# FPGA.net
KiCad netlist of a schematic drawn in Altium Designer
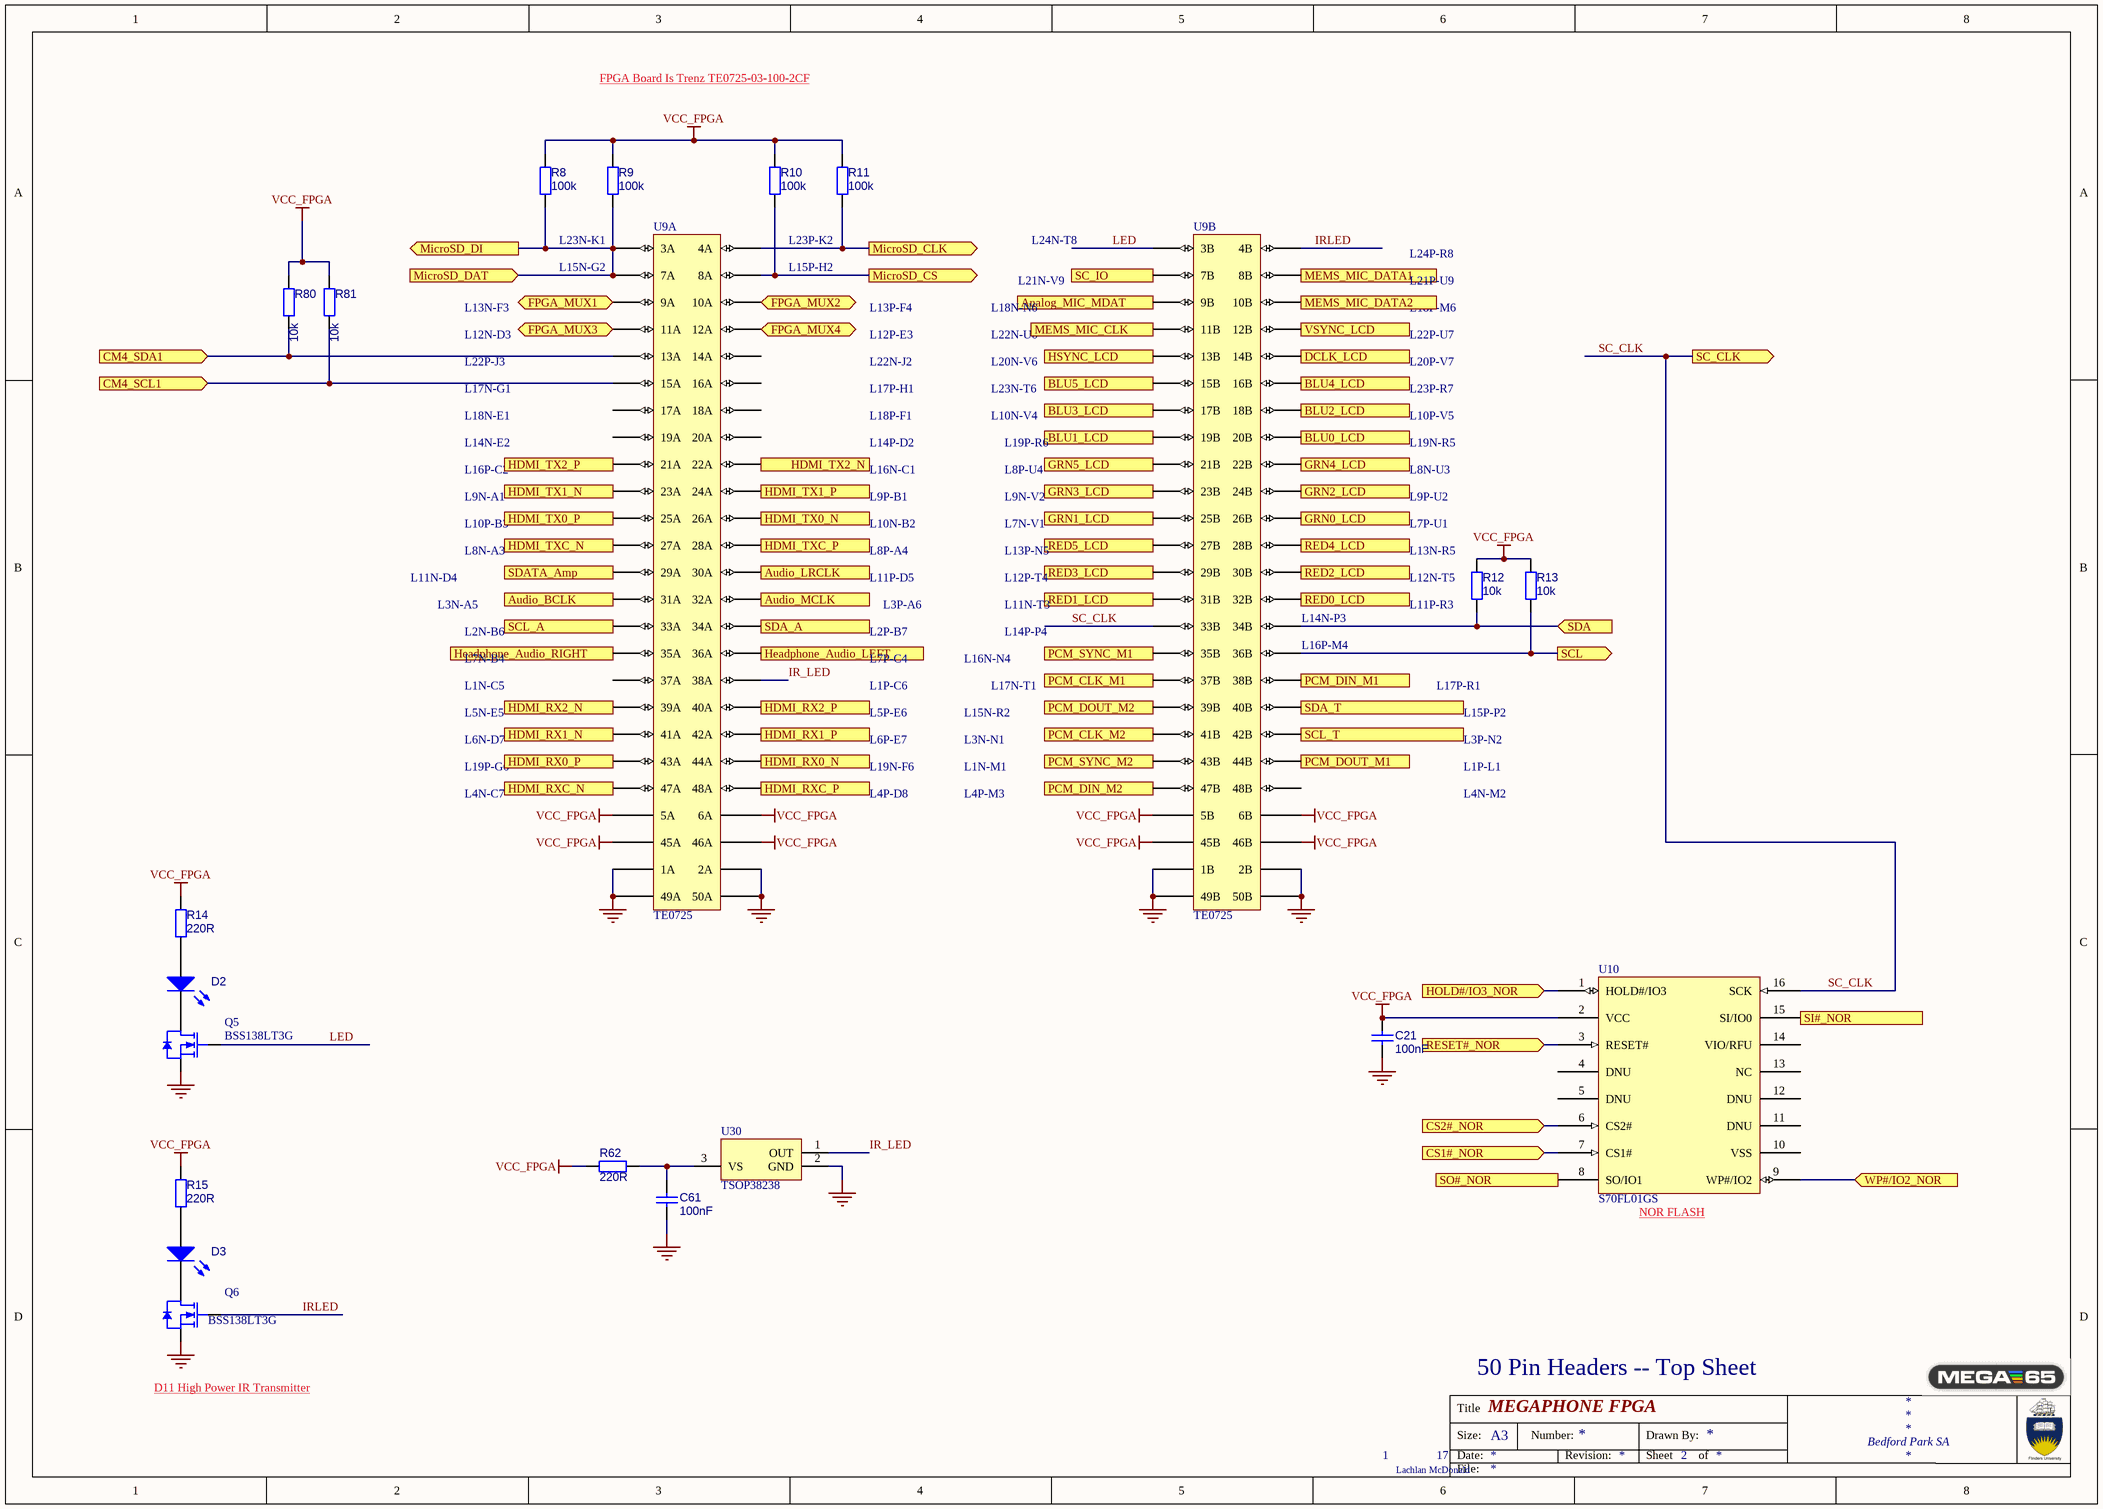
[diagram p0: FPGA.SchDoc]

(export (version "E")
  (design (tool "Eeschema 10.0.6"))
  (components
    (comp (ref "C21")
      (value "100nF")
      (footprint "0603_CAP UF HD")
      (description "Capacitor")
      (libsource (lib "Workshop Library 2010_06_24") (part "Cap"))
    )
    (comp (ref "C61")
      (value "100nF")
      (footprint "0603_CAP UF HD")
      (description "Capacitor")
      (libsource (lib "Workshop Library 2010_06_24") (part "Cap"))
    )
    (comp (ref "D2")
      (value "~")
      (footprint "LED 3mm Red")
      (description "LED")
      (libsource (lib "Workshop Library 2010_06_24") (part "LED"))
    )
    (comp (ref "D3")
      (value "~")
      (footprint "LED 3mm Red")
      (description "LED")
      (libsource (lib "Workshop Library 2010_06_24") (part "LED"))
    )
    (comp (ref "Q5")
      (value "BSS138LT3G")
      (footprint "SOT-23")
      (description "Power MOSFET, 200 mA, 50 V, N-Channel, 3-Pin SOT-23, Pb-Free, Tape and Reel")
      (fields
        (field (name "MANUFACTURER") "On Semiconductor")
        (field (name "ELEMENT 14 PART NUMBER") "1431319")
      )
      (libsource (lib "Workshop Library 2010_06_24") (part "BSS138LT3G"))
    )
    (comp (ref "Q6")
      (value "BSS138LT3G")
      (footprint "SOT-23")
      (description "Power MOSFET, 200 mA, 50 V, N-Channel, 3-Pin SOT-23, Pb-Free, Tape and Reel")
      (fields
        (field (name "MANUFACTURER") "On Semiconductor")
        (field (name "ELEMENT 14 PART NUMBER") "1431319")
      )
      (libsource (lib "Workshop Library 2010_06_24") (part "BSS138LT3G"))
    )
    (comp (ref "R8")
      (value "100k")
      (footprint "0603-RESISTOR HD")
      (description "Resistor")
      (libsource (lib "MEGAphone") (part "Resistor"))
    )
    (comp (ref "R9")
      (value "100k")
      (footprint "0603-RESISTOR HD")
      (description "Resistor")
      (libsource (lib "MEGAphone") (part "Resistor"))
    )
    (comp (ref "R10")
      (value "100k")
      (footprint "0603-RESISTOR HD")
      (description "Resistor")
      (libsource (lib "MEGAphone") (part "Resistor"))
    )
    (comp (ref "R11")
      (value "100k")
      (footprint "0603-RESISTOR HD")
      (description "Resistor")
      (libsource (lib "MEGAphone") (part "Resistor"))
    )
    (comp (ref "R12")
      (value "10k")
      (footprint "0603-RESISTOR HD")
      (description "Resistor")
      (libsource (lib "Workshop Library 2010_06_24") (part "Resistor"))
    )
    (comp (ref "R13")
      (value "10k")
      (footprint "0603-RESISTOR HD")
      (description "Resistor")
      (libsource (lib "Workshop Library 2010_06_24") (part "Resistor"))
    )
    (comp (ref "R14")
      (value "220R")
      (footprint "0603-RESISTOR HD")
      (description "Resistor")
      (libsource (lib "Workshop Library 2010_06_24") (part "Resistor"))
    )
    (comp (ref "R15")
      (value "220R")
      (footprint "0603-RESISTOR HD")
      (description "Resistor")
      (libsource (lib "Workshop Library 2010_06_24") (part "Resistor"))
    )
    (comp (ref "R62")
      (value "220R")
      (footprint "0603-RESISTOR HD")
      (description "Resistor")
      (libsource (lib "") (part "Resistor_1"))
    )
    (comp (ref "R80")
      (value "10k")
      (footprint "0603-RESISTOR HD")
      (description "Resistor")
      (libsource (lib "Workshop Library 2010_06_24") (part "Resistor"))
    )
    (comp (ref "R81")
      (value "10k")
      (footprint "0603-RESISTOR HD")
      (description "Resistor")
      (libsource (lib "Workshop Library 2010_06_24") (part "Resistor"))
    )
    (comp (ref "U9")
      (value "TE0725")
      (footprint "Trenz TE-0725")
      (description "FPGA Module Xilinx Artix-7 100T, optical transceiver")
      (fields (field (name "MANUFACTURER") "TE Connectivity"))
      (libsource (lib "Workshop Library 2010_06_24") (part "TRENZ TE0725"))
    )
    (comp (ref "U10")
      (value "S70FL01GS")
      (footprint "S70FL01GS")
      (fields (field (name "MANUFACTURER") "S70FL01GSDPMFI010"))
      (libsource (lib "Schlib1") (part "NOR Flash"))
    )
    (comp (ref "U30")
      (value "TSOP38238")
      (footprint "VISH-TSOP38238")
      (description "IR Receiver Modules for Remote Control System, 2.5 to 5.5 V, -25 to 85 degC, 3-Pin THD, RoHS, Bulk")
      (fields (field (name "TOLERANCE") "30ppm"))
      (libsource (lib "Altium Content Vault") (part "VISH-TSOP38238-3"))
    )
  )
  (nets
    (net (code "1") (name "/Analog_MIC_MDAT") (class "Default")
      (node (ref "U9") (pin "9B") (pinfunction "9B_9B") (pintype "bidirectional"))
    )
    (net (code "2") (name "/Audio_BCLK") (class "Default")
      (node (ref "U9") (pin "31A") (pinfunction "31A_31A") (pintype "bidirectional"))
    )
    (net (code "3") (name "/Audio_LRCLK") (class "Default")
      (node (ref "U9") (pin "30A") (pinfunction "30A_30A") (pintype "bidirectional"))
    )
    (net (code "4") (name "/Audio_MCLK") (class "Default")
      (node (ref "U9") (pin "32A") (pinfunction "32A_32A") (pintype "bidirectional"))
    )
    (net (code "5") (name "/BLU0_LCD") (class "Default")
      (node (ref "U9") (pin "20B") (pinfunction "20B_20B") (pintype "bidirectional"))
    )
    (net (code "6") (name "/BLU1_LCD") (class "Default")
      (node (ref "U9") (pin "19B") (pinfunction "19B_19B") (pintype "bidirectional"))
    )
    (net (code "7") (name "/BLU2_LCD") (class "Default")
      (node (ref "U9") (pin "18B") (pinfunction "18B_18B") (pintype "bidirectional"))
    )
    (net (code "8") (name "/BLU3_LCD") (class "Default")
      (node (ref "U9") (pin "17B") (pinfunction "17B_17B") (pintype "bidirectional"))
    )
    (net (code "9") (name "/BLU4_LCD") (class "Default")
      (node (ref "U9") (pin "16B") (pinfunction "16B_16B") (pintype "bidirectional"))
    )
    (net (code "10") (name "/BLU5_LCD") (class "Default")
      (node (ref "U9") (pin "15B") (pinfunction "15B_15B") (pintype "bidirectional"))
    )
    (net (code "11") (name "/CM4_SCL1") (class "Default")
      (node (ref "R81") (pin "2") (pinfunction "2_2") (pintype "passive"))
      (node (ref "U9") (pin "15A") (pinfunction "15A_15A") (pintype "bidirectional"))
    )
    (net (code "12") (name "/CM4_SDA1") (class "Default")
      (node (ref "R80") (pin "2") (pinfunction "2_2") (pintype "passive"))
      (node (ref "U9") (pin "13A") (pinfunction "13A_13A") (pintype "bidirectional"))
    )
    (net (code "13") (name "/CS1#_NOR") (class "Default")
      (node (ref "U10") (pin "7") (pinfunction "CS1#_7") (pintype "input"))
    )
    (net (code "14") (name "/CS2#_NOR") (class "Default")
      (node (ref "U10") (pin "6") (pinfunction "CS2#_6") (pintype "input"))
    )
    (net (code "15") (name "/DCLK_LCD") (class "Default")
      (node (ref "U9") (pin "14B") (pinfunction "14B_14B") (pintype "bidirectional"))
    )
    (net (code "16") (name "/FPGA_MUX1") (class "Default")
      (node (ref "U9") (pin "9A") (pinfunction "9A_9A") (pintype "bidirectional"))
    )
    (net (code "17") (name "/FPGA_MUX2") (class "Default")
      (node (ref "U9") (pin "10A") (pinfunction "10A_10A") (pintype "bidirectional"))
    )
    (net (code "18") (name "/FPGA_MUX3") (class "Default")
      (node (ref "U9") (pin "11A") (pinfunction "11A_11A") (pintype "bidirectional"))
    )
    (net (code "19") (name "/FPGA_MUX4") (class "Default")
      (node (ref "U9") (pin "12A") (pinfunction "12A_12A") (pintype "bidirectional"))
    )
    (net (code "20") (name "/GRN0_LCD") (class "Default")
      (node (ref "U9") (pin "26B") (pinfunction "26B_26B") (pintype "bidirectional"))
    )
    (net (code "21") (name "/GRN1_LCD") (class "Default")
      (node (ref "U9") (pin "25B") (pinfunction "25B_25B") (pintype "bidirectional"))
    )
    (net (code "22") (name "/GRN2_LCD") (class "Default")
      (node (ref "U9") (pin "24B") (pinfunction "24B_24B") (pintype "bidirectional"))
    )
    (net (code "23") (name "/GRN3_LCD") (class "Default")
      (node (ref "U9") (pin "23B") (pinfunction "23B_23B") (pintype "bidirectional"))
    )
    (net (code "24") (name "/GRN4_LCD") (class "Default")
      (node (ref "U9") (pin "22B") (pinfunction "22B_22B") (pintype "bidirectional"))
    )
    (net (code "25") (name "/GRN5_LCD") (class "Default")
      (node (ref "U9") (pin "21B") (pinfunction "21B_21B") (pintype "bidirectional"))
    )
    (net (code "26") (name "/HDMI_RX0_N") (class "Default")
      (node (ref "U9") (pin "44A") (pinfunction "44A_44A") (pintype "bidirectional"))
    )
    (net (code "27") (name "/HDMI_RX0_P") (class "Default")
      (node (ref "U9") (pin "43A") (pinfunction "43A_43A") (pintype "bidirectional"))
    )
    (net (code "28") (name "/HDMI_RX1_N") (class "Default")
      (node (ref "U9") (pin "41A") (pinfunction "41A_41A") (pintype "bidirectional"))
    )
    (net (code "29") (name "/HDMI_RX1_P") (class "Default")
      (node (ref "U9") (pin "42A") (pinfunction "42A_42A") (pintype "bidirectional"))
    )
    (net (code "30") (name "/HDMI_RX2_N") (class "Default")
      (node (ref "U9") (pin "39A") (pinfunction "39A_39A") (pintype "bidirectional"))
    )
    (net (code "31") (name "/HDMI_RX2_P") (class "Default")
      (node (ref "U9") (pin "40A") (pinfunction "40A_40A") (pintype "bidirectional"))
    )
    (net (code "32") (name "/HDMI_RXC_N") (class "Default")
      (node (ref "U9") (pin "47A") (pinfunction "47A_47A") (pintype "bidirectional"))
    )
    (net (code "33") (name "/HDMI_RXC_P") (class "Default")
      (node (ref "U9") (pin "48A") (pinfunction "48A_48A") (pintype "bidirectional"))
    )
    (net (code "34") (name "/HDMI_TX0_N") (class "Default")
      (node (ref "U9") (pin "26A") (pinfunction "26A_26A") (pintype "bidirectional"))
    )
    (net (code "35") (name "/HDMI_TX0_P") (class "Default")
      (node (ref "U9") (pin "25A") (pinfunction "25A_25A") (pintype "bidirectional"))
    )
    (net (code "36") (name "/HDMI_TX1_N") (class "Default")
      (node (ref "U9") (pin "23A") (pinfunction "23A_23A") (pintype "bidirectional"))
    )
    (net (code "37") (name "/HDMI_TX1_P") (class "Default")
      (node (ref "U9") (pin "24A") (pinfunction "24A_24A") (pintype "bidirectional"))
    )
    (net (code "38") (name "/HDMI_TX2_N") (class "Default")
      (node (ref "U9") (pin "22A") (pinfunction "22A_22A") (pintype "bidirectional"))
    )
    (net (code "39") (name "/HDMI_TX2_P") (class "Default")
      (node (ref "U9") (pin "21A") (pinfunction "21A_21A") (pintype "bidirectional"))
    )
    (net (code "40") (name "/HDMI_TXC_N") (class "Default")
      (node (ref "U9") (pin "27A") (pinfunction "27A_27A") (pintype "bidirectional"))
    )
    (net (code "41") (name "/HDMI_TXC_P") (class "Default")
      (node (ref "U9") (pin "28A") (pinfunction "28A_28A") (pintype "bidirectional"))
    )
    (net (code "42") (name "/HOLD#{slash}IO3_NOR") (class "Default")
      (node (ref "U10") (pin "1") (pinfunction "HOLD#/IO3_1") (pintype "bidirectional"))
    )
    (net (code "43") (name "/HSYNC_LCD") (class "Default")
      (node (ref "U9") (pin "13B") (pinfunction "13B_13B") (pintype "bidirectional"))
    )
    (net (code "44") (name "/Headphone_Audio_LEFT") (class "Default")
      (node (ref "U9") (pin "36A") (pinfunction "36A_36A") (pintype "bidirectional"))
    )
    (net (code "45") (name "/Headphone_Audio_RIGHT") (class "Default")
      (node (ref "U9") (pin "35A") (pinfunction "35A_35A") (pintype "bidirectional"))
    )
    (net (code "46") (name "/IRLED") (class "Default")
      (node (ref "Q6") (pin "1") (pinfunction "G_1") (pintype "passive"))
      (node (ref "U9") (pin "4B") (pinfunction "4B_4B") (pintype "bidirectional"))
    )
    (net (code "47") (name "/IR_LED") (class "Default")
      (node (ref "U30") (pin "1") (pinfunction "OUT_1") (pintype "power_in"))
      (node (ref "U9") (pin "38A") (pinfunction "38A_38A") (pintype "bidirectional"))
    )
    (net (code "48") (name "/LED") (class "Default")
      (node (ref "Q5") (pin "1") (pinfunction "G_1") (pintype "passive"))
      (node (ref "U9") (pin "3B") (pinfunction "3B_3B") (pintype "bidirectional"))
    )
    (net (code "49") (name "/MEMS_MIC_CLK") (class "Default")
      (node (ref "U9") (pin "11B") (pinfunction "11B_11B") (pintype "bidirectional"))
    )
    (net (code "50") (name "/MEMS_MIC_DATA1") (class "Default")
      (node (ref "U9") (pin "8B") (pinfunction "8B_8B") (pintype "bidirectional"))
    )
    (net (code "51") (name "/MEMS_MIC_DATA2") (class "Default")
      (node (ref "U9") (pin "10B") (pinfunction "10B_10B") (pintype "bidirectional"))
    )
    (net (code "52") (name "/MicroSD_CLK") (class "Default")
      (node (ref "R11") (pin "2") (pinfunction "2_2") (pintype "passive"))
      (node (ref "U9") (pin "4A") (pinfunction "4A_4A") (pintype "bidirectional"))
    )
    (net (code "53") (name "/MicroSD_CS") (class "Default")
      (node (ref "R10") (pin "2") (pinfunction "2_2") (pintype "passive"))
      (node (ref "U9") (pin "8A") (pinfunction "8A_8A") (pintype "bidirectional"))
    )
    (net (code "54") (name "/MicroSD_DAT") (class "Default")
      (node (ref "R8") (pin "2") (pinfunction "2_2") (pintype "passive"))
      (node (ref "R9") (pin "2") (pinfunction "2_2") (pintype "passive"))
      (node (ref "U9") (pin "3A") (pinfunction "3A_3A") (pintype "bidirectional"))
      (node (ref "U9") (pin "7A") (pinfunction "7A_7A") (pintype "bidirectional"))
    )
    (net (code "55") (name "/PCM_CLK_M1") (class "Default")
      (node (ref "U9") (pin "37B") (pinfunction "37B_37B") (pintype "bidirectional"))
    )
    (net (code "56") (name "/PCM_CLK_M2") (class "Default")
      (node (ref "U9") (pin "41B") (pinfunction "41B_41B") (pintype "bidirectional"))
    )
    (net (code "57") (name "/PCM_DIN_M1") (class "Default")
      (node (ref "U9") (pin "38B") (pinfunction "38B_38B") (pintype "bidirectional"))
    )
    (net (code "58") (name "/PCM_DIN_M2") (class "Default")
      (node (ref "U9") (pin "47B") (pinfunction "47B_47B") (pintype "bidirectional"))
    )
    (net (code "59") (name "/PCM_DOUT_M1") (class "Default")
      (node (ref "U9") (pin "44B") (pinfunction "44B_44B") (pintype "bidirectional"))
    )
    (net (code "60") (name "/PCM_DOUT_M2") (class "Default")
      (node (ref "U9") (pin "39B") (pinfunction "39B_39B") (pintype "bidirectional"))
    )
    (net (code "61") (name "/PCM_SYNC_M1") (class "Default")
      (node (ref "U9") (pin "35B") (pinfunction "35B_35B") (pintype "bidirectional"))
    )
    (net (code "62") (name "/PCM_SYNC_M2") (class "Default")
      (node (ref "U9") (pin "43B") (pinfunction "43B_43B") (pintype "bidirectional"))
    )
    (net (code "63") (name "/RED0_LCD") (class "Default")
      (node (ref "U9") (pin "32B") (pinfunction "32B_32B") (pintype "bidirectional"))
    )
    (net (code "64") (name "/RED1_LCD") (class "Default")
      (node (ref "U9") (pin "31B") (pinfunction "31B_31B") (pintype "bidirectional"))
    )
    (net (code "65") (name "/RED2_LCD") (class "Default")
      (node (ref "U9") (pin "30B") (pinfunction "30B_30B") (pintype "bidirectional"))
    )
    (net (code "66") (name "/RED3_LCD") (class "Default")
      (node (ref "U9") (pin "29B") (pinfunction "29B_29B") (pintype "bidirectional"))
    )
    (net (code "67") (name "/RED4_LCD") (class "Default")
      (node (ref "U9") (pin "28B") (pinfunction "28B_28B") (pintype "bidirectional"))
    )
    (net (code "68") (name "/RED5_LCD") (class "Default")
      (node (ref "U9") (pin "27B") (pinfunction "27B_27B") (pintype "bidirectional"))
    )
    (net (code "69") (name "/RESET#_NOR") (class "Default")
      (node (ref "U10") (pin "3") (pinfunction "RESET#_3") (pintype "input"))
    )
    (net (code "70") (name "/SCL") (class "Default")
      (node (ref "R13") (pin "2") (pinfunction "2_2") (pintype "passive"))
      (node (ref "U9") (pin "36B") (pinfunction "36B_36B") (pintype "bidirectional"))
    )
    (net (code "71") (name "/SCL_A") (class "Default")
      (node (ref "U9") (pin "33A") (pinfunction "33A_33A") (pintype "bidirectional"))
    )
    (net (code "72") (name "/SCL_T") (class "Default")
      (node (ref "U9") (pin "42B") (pinfunction "42B_42B") (pintype "bidirectional"))
    )
    (net (code "73") (name "/SC_CLK") (class "Default")
      (node (ref "U10") (pin "16") (pinfunction "SCK_16") (pintype "input"))
      (node (ref "U9") (pin "33B") (pinfunction "33B_33B") (pintype "bidirectional"))
    )
    (net (code "74") (name "/SC_IO") (class "Default")
      (node (ref "U9") (pin "7B") (pinfunction "7B_7B") (pintype "bidirectional"))
    )
    (net (code "75") (name "/SDA") (class "Default")
      (node (ref "R12") (pin "2") (pinfunction "2_2") (pintype "passive"))
      (node (ref "U9") (pin "34B") (pinfunction "34B_34B") (pintype "bidirectional"))
    )
    (net (code "76") (name "/SDATA_Amp") (class "Default")
      (node (ref "U9") (pin "29A") (pinfunction "29A_29A") (pintype "bidirectional"))
    )
    (net (code "77") (name "/SDA_A") (class "Default")
      (node (ref "U9") (pin "34A") (pinfunction "34A_34A") (pintype "bidirectional"))
    )
    (net (code "78") (name "/SDA_T") (class "Default")
      (node (ref "U9") (pin "40B") (pinfunction "40B_40B") (pintype "bidirectional"))
    )
    (net (code "79") (name "/SI#_NOR") (class "Default")
      (node (ref "U10") (pin "15") (pinfunction "SI/IO0_15") (pintype "passive"))
    )
    (net (code "80") (name "/SO#_NOR") (class "Default")
      (node (ref "U10") (pin "8") (pinfunction "SO/IO1_8") (pintype "passive"))
    )
    (net (code "81") (name "/VSYNC_LCD") (class "Default")
      (node (ref "U9") (pin "12B") (pinfunction "12B_12B") (pintype "bidirectional"))
    )
    (net (code "82") (name "/WP#{slash}IO2_NOR") (class "Default")
      (node (ref "U10") (pin "9") (pinfunction "WP#/IO2_9") (pintype "bidirectional"))
    )
    (net (code "83") (name "GND") (class "Default")
      (node (ref "C21") (pin "2") (pinfunction "2_2") (pintype "passive"))
      (node (ref "C61") (pin "2") (pinfunction "2_2") (pintype "passive"))
      (node (ref "Q5") (pin "2") (pinfunction "S_2") (pintype "passive"))
      (node (ref "Q6") (pin "2") (pinfunction "S_2") (pintype "passive"))
      (node (ref "U30") (pin "2") (pinfunction "GND_2") (pintype "power_in"))
      (node (ref "U9") (pin "1A") (pinfunction "1A_1A") (pintype "power_in"))
      (node (ref "U9") (pin "1B") (pinfunction "1B_1B") (pintype "power_in"))
      (node (ref "U9") (pin "2A") (pinfunction "2A_2A") (pintype "power_in"))
      (node (ref "U9") (pin "2B") (pinfunction "2B_2B") (pintype "power_in"))
      (node (ref "U9") (pin "49A") (pinfunction "49A_49A") (pintype "power_in"))
      (node (ref "U9") (pin "49B") (pinfunction "49B_49B") (pintype "power_in"))
      (node (ref "U9") (pin "50A") (pinfunction "50A_50A") (pintype "power_in"))
      (node (ref "U9") (pin "50B") (pinfunction "50B_50B") (pintype "power_in"))
    )
    (net (code "84") (name "Net-(D2-PadA)") (class "Default")
      (node (ref "D2") (pin "A") (pinfunction "A_A") (pintype "passive"))
      (node (ref "R14") (pin "2") (pinfunction "2_2") (pintype "passive"))
    )
    (net (code "85") (name "Net-(D3-PadA)") (class "Default")
      (node (ref "D3") (pin "A") (pinfunction "A_A") (pintype "passive"))
      (node (ref "R15") (pin "2") (pinfunction "2_2") (pintype "passive"))
    )
    (net (code "86") (name "Net-(Q5-D)") (class "Default")
      (node (ref "D2") (pin "K") (pinfunction "K_K") (pintype "passive"))
      (node (ref "Q5") (pin "3") (pinfunction "D_3") (pintype "passive"))
    )
    (net (code "87") (name "Net-(Q6-D)") (class "Default")
      (node (ref "D3") (pin "K") (pinfunction "K_K") (pintype "passive"))
      (node (ref "Q6") (pin "3") (pinfunction "D_3") (pintype "passive"))
    )
    (net (code "88") (name "Net-(U30-VS)") (class "Default")
      (node (ref "C61") (pin "1") (pinfunction "1_1") (pintype "passive"))
      (node (ref "R62") (pin "2") (pinfunction "2_2") (pintype "passive"))
      (node (ref "U30") (pin "3") (pinfunction "VS_3") (pintype "power_in"))
    )
    (net (code "89") (name "VCC_FPGA") (class "Default")
      (node (ref "C21") (pin "1") (pinfunction "1_1") (pintype "passive"))
      (node (ref "R10") (pin "1") (pinfunction "1_1") (pintype "passive"))
      (node (ref "R11") (pin "1") (pinfunction "1_1") (pintype "passive"))
      (node (ref "R12") (pin "1") (pinfunction "1_1") (pintype "passive"))
      (node (ref "R13") (pin "1") (pinfunction "1_1") (pintype "passive"))
      (node (ref "R14") (pin "1") (pinfunction "1_1") (pintype "passive"))
      (node (ref "R15") (pin "1") (pinfunction "1_1") (pintype "passive"))
      (node (ref "R62") (pin "1") (pinfunction "1_1") (pintype "passive"))
      (node (ref "R8") (pin "1") (pinfunction "1_1") (pintype "passive"))
      (node (ref "R80") (pin "1") (pinfunction "1_1") (pintype "passive"))
      (node (ref "R81") (pin "1") (pinfunction "1_1") (pintype "passive"))
      (node (ref "R9") (pin "1") (pinfunction "1_1") (pintype "passive"))
      (node (ref "U10") (pin "2") (pinfunction "VCC_2") (pintype "power_in"))
      (node (ref "U9") (pin "45A") (pinfunction "45A_45A") (pintype "power_in"))
      (node (ref "U9") (pin "45B") (pinfunction "45B_45B") (pintype "power_in"))
      (node (ref "U9") (pin "46A") (pinfunction "46A_46A") (pintype "power_in"))
      (node (ref "U9") (pin "46B") (pinfunction "46B_46B") (pintype "power_in"))
      (node (ref "U9") (pin "5A") (pinfunction "5A_5A") (pintype "power_in"))
      (node (ref "U9") (pin "5B") (pinfunction "5B_5B") (pintype "power_in"))
      (node (ref "U9") (pin "6A") (pinfunction "6A_6A") (pintype "power_in"))
      (node (ref "U9") (pin "6B") (pinfunction "6B_6B") (pintype "power_in"))
    )
    (net (code "90") (name "unconnected-(U9-Pad14A)") (class "Default")
      (node (ref "U9") (pin "14A") (pinfunction "14A_14A") (pintype "bidirectional"))
    )
    (net (code "91") (name "unconnected-(U9-Pad16A)") (class "Default")
      (node (ref "U9") (pin "16A") (pinfunction "16A_16A") (pintype "bidirectional"))
    )
    (net (code "92") (name "unconnected-(U9-Pad17A)") (class "Default")
      (node (ref "U9") (pin "17A") (pinfunction "17A_17A") (pintype "bidirectional"))
    )
    (net (code "93") (name "unconnected-(U9-Pad18A)") (class "Default")
      (node (ref "U9") (pin "18A") (pinfunction "18A_18A") (pintype "bidirectional"))
    )
    (net (code "94") (name "unconnected-(U9-Pad19A)") (class "Default")
      (node (ref "U9") (pin "19A") (pinfunction "19A_19A") (pintype "bidirectional"))
    )
    (net (code "95") (name "unconnected-(U9-Pad20A)") (class "Default")
      (node (ref "U9") (pin "20A") (pinfunction "20A_20A") (pintype "bidirectional"))
    )
    (net (code "96") (name "unconnected-(U9-Pad37A)") (class "Default")
      (node (ref "U9") (pin "37A") (pinfunction "37A_37A") (pintype "bidirectional"))
    )
    (net (code "97") (name "unconnected-(U9-Pad48B)") (class "Default")
      (node (ref "U9") (pin "48B") (pinfunction "48B_48B") (pintype "bidirectional"))
    )
    (net (code "98") (name "unconnected-(U10-DNU-Pad4)") (class "Default")
      (node (ref "U10") (pin "4") (pinfunction "DNU_4") (pintype "passive"))
    )
    (net (code "99") (name "unconnected-(U10-DNU-Pad5)") (class "Default")
      (node (ref "U10") (pin "5") (pinfunction "DNU_5") (pintype "passive"))
    )
    (net (code "100") (name "unconnected-(U10-DNU-Pad11)") (class "Default")
      (node (ref "U10") (pin "11") (pinfunction "DNU_11") (pintype "passive"))
    )
    (net (code "101") (name "unconnected-(U10-DNU-Pad12)") (class "Default")
      (node (ref "U10") (pin "12") (pinfunction "DNU_12") (pintype "passive"))
    )
    (net (code "102") (name "unconnected-(U10-NC-Pad13)") (class "Default")
      (node (ref "U10") (pin "13") (pinfunction "NC_13") (pintype "passive"))
    )
    (net (code "103") (name "unconnected-(U10-VIO{slash}RFU-Pad14)") (class "Default")
      (node (ref "U10") (pin "14") (pinfunction "VIO/RFU_14") (pintype "power_in"))
    )
    (net (code "104") (name "unconnected-(U10-VSS-Pad10)") (class "Default")
      (node (ref "U10") (pin "10") (pinfunction "VSS_10") (pintype "power_in"))
    )
  )
)
